# XMC4504.net
KiCad netlist of a schematic drawn in Altium Designer
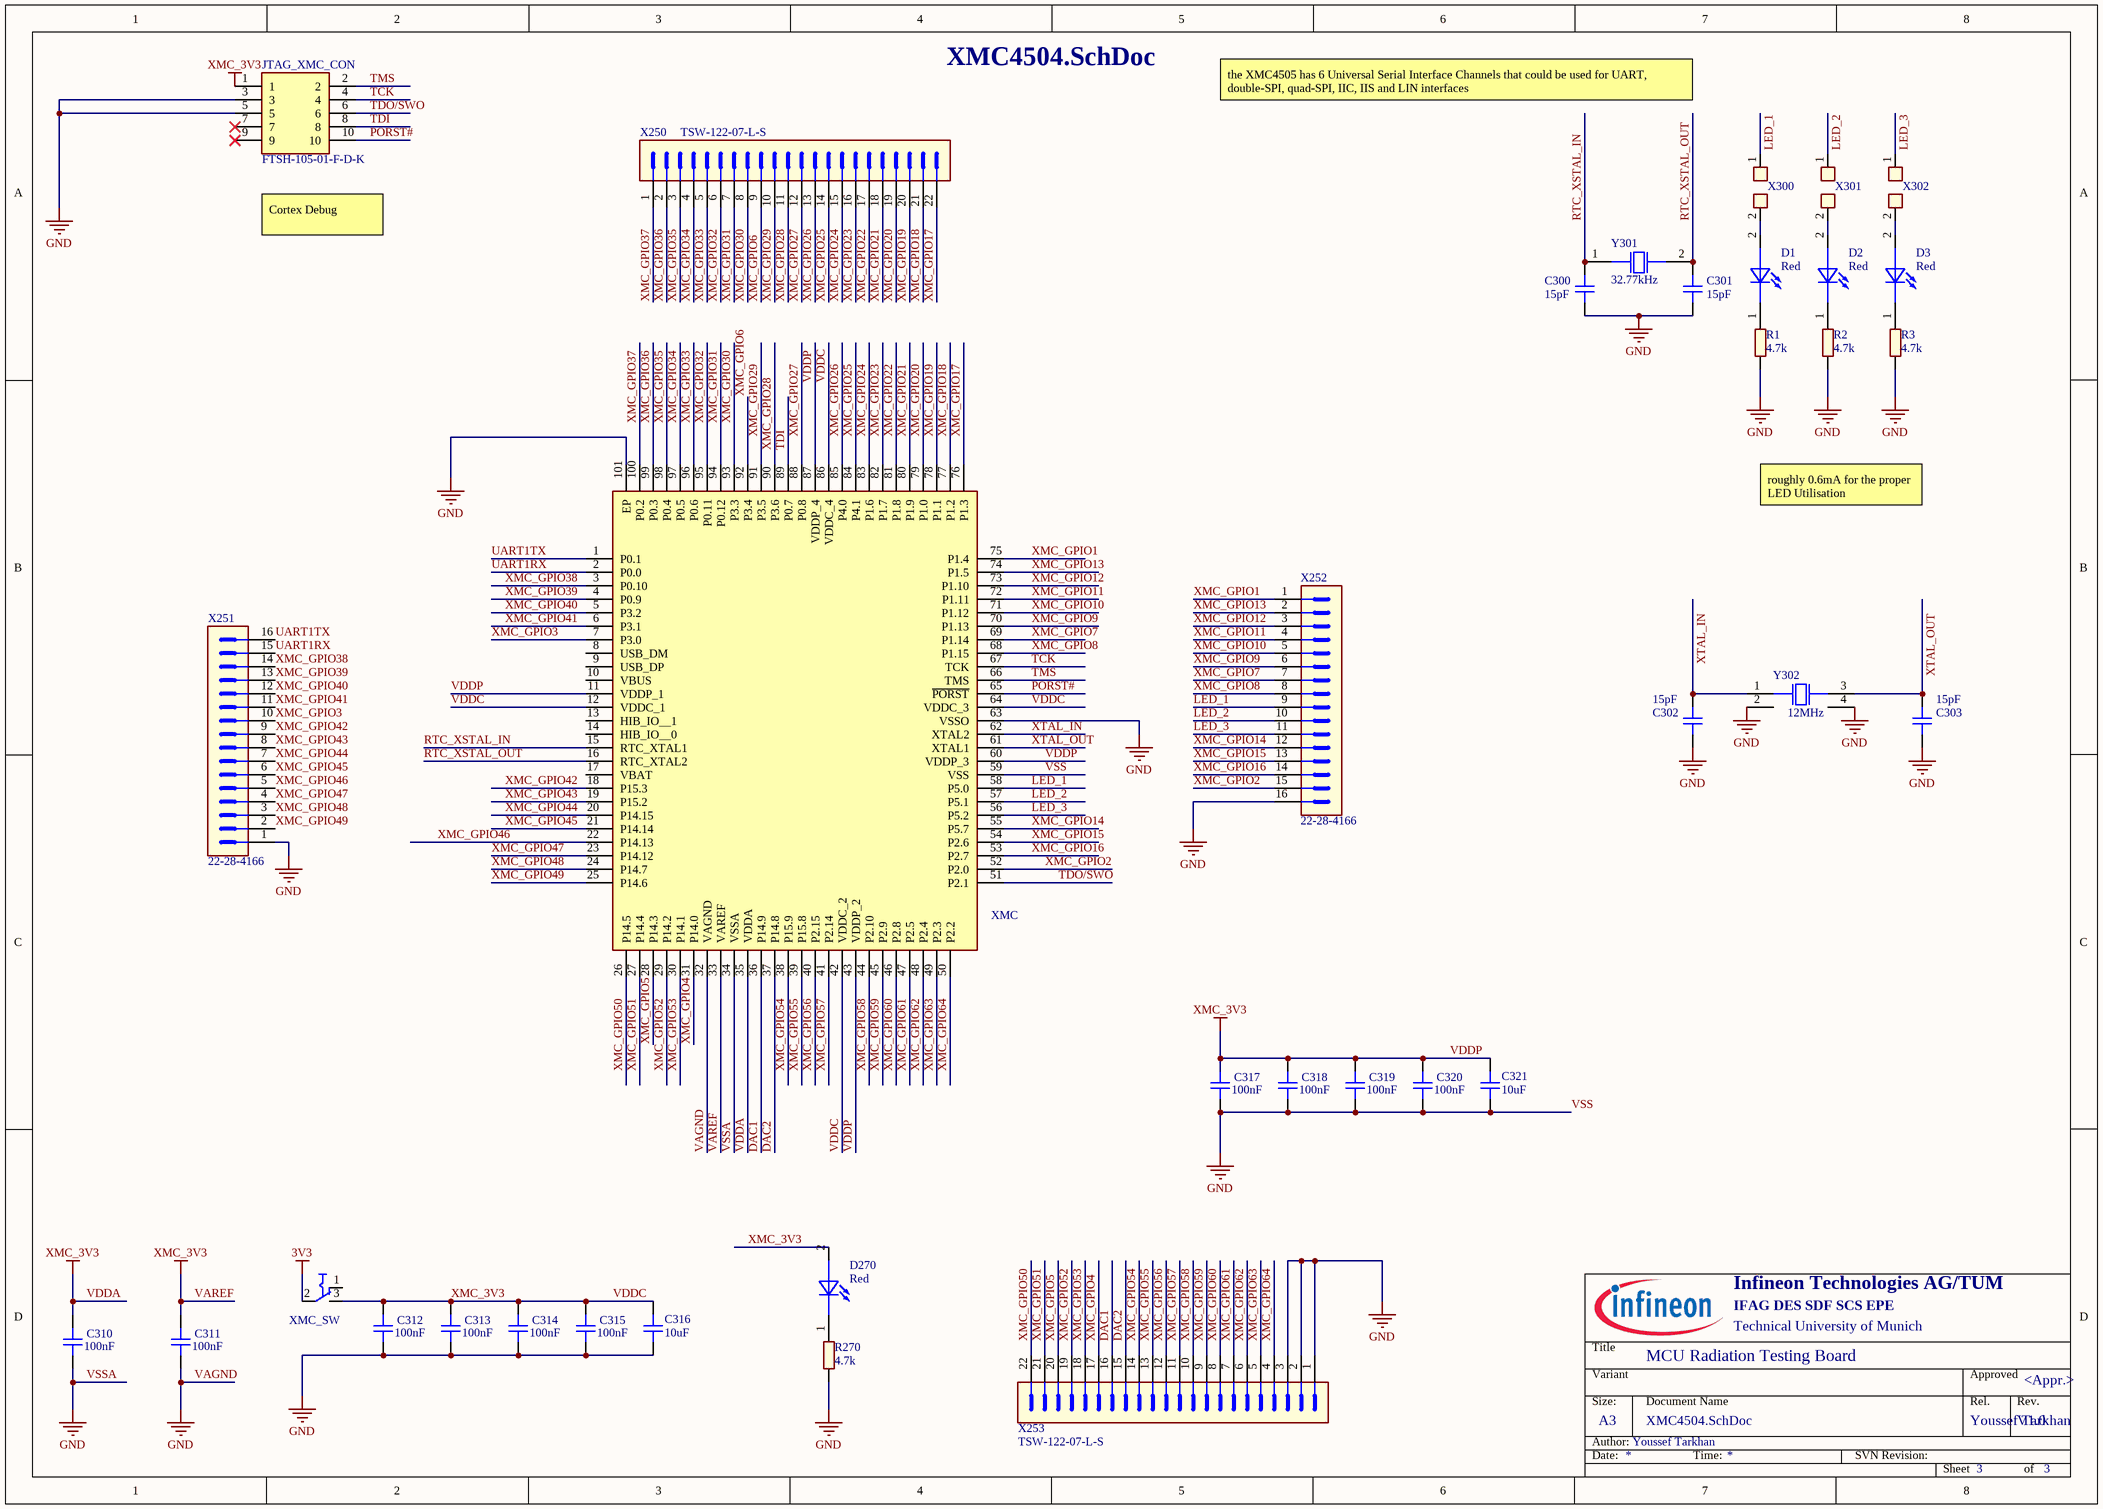
[diagram p0: XMC4504.SchDoc]

(export (version "E")
  (design (tool "Eeschema 10.0.6"))
  (components
    (comp (ref "C300")
      (value "15pF")
      (footprint "CAPC1608X90N")
      (description "CAP / CERA / 15pF / 50V / 2% / C0G (EIA) / NP0 / -55°C to 125°C / 0603(1608) / SMD / -")
      (fields (field (name "LEGACY PARTNUMBER") "CAP01002488") (field (name "MANUFACTURER") "MuRata"))
      (libsource (lib "PCBLibraryData") (part "CAP-SGL-STD-02P_00000001"))
    )
    (comp (ref "C301")
      (value "15pF")
      (footprint "CAPC1608X90N")
      (description "CAP / CERA / 15pF / 50V / 2% / C0G (EIA) / NP0 / -55°C to 125°C / 0603(1608) / SMD / -")
      (fields (field (name "LEGACY PARTNUMBER") "CAP01002488") (field (name "MANUFACTURER") "MuRata"))
      (libsource (lib "PCBLibraryData") (part "CAP-SGL-STD-02P_00000001"))
    )
    (comp (ref "C302")
      (value "15pF")
      (footprint "CAPC1608X90N")
      (description "CAP / CERA / 15pF / 50V / 2% / C0G (EIA) / NP0 / -55°C to 125°C / 0603(1608) / SMD / -")
      (fields (field (name "LEGACY PARTNUMBER") "CAP01002488") (field (name "MANUFACTURER") "MuRata"))
      (libsource (lib "PCBLibraryData") (part "CAP-SGL-STD-02P_00000001"))
    )
    (comp (ref "C303")
      (value "15pF")
      (footprint "CAPC1608X90N")
      (description "CAP / CERA / 15pF / 50V / 2% / C0G (EIA) / NP0 / -55°C to 125°C / 0603(1608) / SMD / -")
      (fields (field (name "LEGACY PARTNUMBER") "CAP01002488") (field (name "MANUFACTURER") "MuRata"))
      (libsource (lib "PCBLibraryData") (part "CAP-SGL-STD-02P_00000001"))
    )
    (comp (ref "C310")
      (value "100nF")
      (footprint "CAPC1608X90N-2")
      (description "CAP / CERA / 100nF / 50V / 10% / X7R (EIA) / -55°C to 125°C / 0603 / SMD / -")
      (fields (field (name "MANUFACTURER") "AVX"))
      (libsource (lib "PCBLibraryData") (part "CAP-SGL-STD-02P_00000001"))
    )
    (comp (ref "C311")
      (value "100nF")
      (footprint "CAPC1608X90N-2")
      (description "CAP / CERA / 100nF / 50V / 10% / X7R (EIA) / -55°C to 125°C / 0603 / SMD / -")
      (fields (field (name "MANUFACTURER") "AVX"))
      (libsource (lib "PCBLibraryData") (part "CAP-SGL-STD-02P_00000001"))
    )
    (comp (ref "C312")
      (value "100nF")
      (footprint "CAPC1608X90N-2")
      (description "CAP / CERA / 100nF / 50V / 10% / X7R (EIA) / -55°C to 125°C / 0603 / SMD / -")
      (fields (field (name "MANUFACTURER") "AVX"))
      (libsource (lib "PCBLibraryData") (part "CAP-SGL-STD-02P_00000001"))
    )
    (comp (ref "C313")
      (value "100nF")
      (footprint "CAPC1608X90N-2")
      (description "CAP / CERA / 100nF / 50V / 10% / X7R (EIA) / -55°C to 125°C / 0603 / SMD / -")
      (fields (field (name "MANUFACTURER") "AVX"))
      (libsource (lib "PCBLibraryData") (part "CAP-SGL-STD-02P_00000001"))
    )
    (comp (ref "C314")
      (value "100nF")
      (footprint "CAPC1608X90N-2")
      (description "CAP / CERA / 100nF / 50V / 10% / X7R (EIA) / -55°C to 125°C / 0603 / SMD / -")
      (fields (field (name "MANUFACTURER") "AVX"))
      (libsource (lib "PCBLibraryData") (part "CAP-SGL-STD-02P_00000001"))
    )
    (comp (ref "C315")
      (value "100nF")
      (footprint "CAPC1608X90N-2")
      (description "CAP / CERA / 100nF / 50V / 10% / X7R (EIA) / -55°C to 125°C / 0603 / SMD / -")
      (fields (field (name "MANUFACTURER") "AVX"))
      (libsource (lib "PCBLibraryData") (part "CAP-SGL-STD-02P_00000001"))
    )
    (comp (ref "C316")
      (value "10uF")
      (footprint "CAPC3216X190N-1")
      (description "CAP / CERA / 10uF / 50V / 20% / X5R (EIA) / -55°C to 85°C / 1206 (3216) / SMD / -")
      (fields (field (name "MANUFACTURER") "Taiyo Yuden"))
      (libsource (lib "PCBLibraryData") (part "CAP-SGL-STD-02P_00000001"))
    )
    (comp (ref "C317")
      (value "100nF")
      (footprint "CAPC1608X90N-2")
      (description "CAP / CERA / 100nF / 50V / 10% / X7R (EIA) / -55°C to 125°C / 0603 / SMD / -")
      (fields (field (name "MANUFACTURER") "AVX"))
      (libsource (lib "PCBLibraryData") (part "CAP-SGL-STD-02P_00000001"))
    )
    (comp (ref "C318")
      (value "100nF")
      (footprint "CAPC1608X90N-2")
      (description "CAP / CERA / 100nF / 50V / 10% / X7R (EIA) / -55°C to 125°C / 0603 / SMD / -")
      (fields (field (name "MANUFACTURER") "AVX"))
      (libsource (lib "PCBLibraryData") (part "CAP-SGL-STD-02P_00000001"))
    )
    (comp (ref "C319")
      (value "100nF")
      (footprint "CAPC1608X90N-2")
      (description "CAP / CERA / 100nF / 50V / 10% / X7R (EIA) / -55°C to 125°C / 0603 / SMD / -")
      (fields (field (name "MANUFACTURER") "AVX"))
      (libsource (lib "PCBLibraryData") (part "CAP-SGL-STD-02P_00000001"))
    )
    (comp (ref "C320")
      (value "100nF")
      (footprint "CAPC1608X90N-2")
      (description "CAP / CERA / 100nF / 50V / 10% / X7R (EIA) / -55°C to 125°C / 0603 / SMD / -")
      (fields (field (name "MANUFACTURER") "AVX"))
      (libsource (lib "PCBLibraryData") (part "CAP-SGL-STD-02P_00000001"))
    )
    (comp (ref "C321")
      (value "10uF")
      (footprint "CAPC3216X190N-1")
      (description "CAP / CERA / 10uF / 50V / 20% / X5R (EIA) / -55°C to 85°C / 1206 (3216) / SMD / -")
      (fields (field (name "MANUFACTURER") "Taiyo Yuden"))
      (libsource (lib "PCBLibraryData") (part "CAP-SGL-STD-02P_00000001"))
    )
    (comp (ref "D1")
      (value "Red")
      (footprint "LEDSC160X80X80-2N-1")
      (description "WL-SMCW SMT Mono-color Chip LED Waterclear, Red,630nm")
      (fields (field (name "MANUFACTURER") "Wurth Elektronik"))
      (libsource (lib "PCBLibraryData") (part "d_led_a"))
    )
    (comp (ref "D2")
      (value "Red")
      (footprint "LEDSC160X80X80-2N-1")
      (description "WL-SMCW SMT Mono-color Chip LED Waterclear, Red,630nm")
      (fields (field (name "MANUFACTURER") "Wurth Elektronik"))
      (libsource (lib "PCBLibraryData") (part "d_led_a"))
    )
    (comp (ref "D3")
      (value "Red")
      (footprint "LEDSC160X80X80-2N-1")
      (description "WL-SMCW SMT Mono-color Chip LED Waterclear, Red,630nm")
      (fields (field (name "MANUFACTURER") "Wurth Elektronik"))
      (libsource (lib "PCBLibraryData") (part "d_led_a"))
    )
    (comp (ref "D270")
      (value "Red")
      (footprint "LEDSC160X80X80-2N-1")
      (description "WL-SMCW SMT Mono-color Chip LED Waterclear, Red,630nm")
      (fields (field (name "MANUFACTURER") "Wurth Elektronik"))
      (libsource (lib "PCBLibraryData") (part "d_led_a"))
    )
    (comp (ref "JTAG_XMC_CON")
      (value "FTSH-105-01-F-D-K")
      (footprint "SamacSys:FTSH-105-XX-YYY-D-K")
      (description "Connector")
      (fields (field (name "MOUSER2 PART NUMBER") "200-FTSH10501FDK"))
      (libsource (lib "*") (part "FTSH-105-01-F-D-K"))
    )
    (comp (ref "R1")
      (value "4.7k")
      (footprint "RESC1609X55N")
      (description "RES / STD / 4.7k / 100mW / 1% / 100ppm/K / -55°C to 155°C / 1.60mm L X 0.85mm W X 0.55mm H / - / -")
      (fields (field (name "MANUFACTURER") "Panasonic"))
      (libsource (lib "PCBLibraryData") (part "RES-SGL-STD-02P_00000006"))
    )
    (comp (ref "R2")
      (value "4.7k")
      (footprint "RESC1609X55N")
      (description "RES / STD / 4.7k / 100mW / 1% / 100ppm/K / -55°C to 155°C / 1.60mm L X 0.85mm W X 0.55mm H / - / -")
      (fields (field (name "MANUFACTURER") "Panasonic"))
      (libsource (lib "PCBLibraryData") (part "RES-SGL-STD-02P_00000006"))
    )
    (comp (ref "R3")
      (value "4.7k")
      (footprint "RESC1609X55N")
      (description "RES / STD / 4.7k / 100mW / 1% / 100ppm/K / -55°C to 155°C / 1.60mm L X 0.85mm W X 0.55mm H / - / -")
      (fields (field (name "MANUFACTURER") "Panasonic"))
      (libsource (lib "PCBLibraryData") (part "RES-SGL-STD-02P_00000006"))
    )
    (comp (ref "R270")
      (value "4.7k")
      (footprint "RESC1609X55N")
      (description "RES / STD / 4.7k / 100mW / 1% / 100ppm/K / -55°C to 155°C / 1.60mm L X 0.85mm W X 0.55mm H / - / -")
      (fields (field (name "MANUFACTURER") "Panasonic"))
      (libsource (lib "PCBLibraryData") (part "RES-SGL-STD-02P_00000006"))
    )
    (comp (ref "X250")
      (value "TSW-122-07-L-S")
      (footprint "CON-M-THT-TSW-122-07-L-S")
      (description "Through hole .025 SQ Post Header, 2.54mm pitch, 22 pin, vertical, single row")
      (fields (field (name "LEGACY PARTNUMBER") "CON01500868") (field (name "MANUFACTURER") "Samtec"))
      (libsource (lib "PCBLibraryData") (part "Header 22"))
    )
    (comp (ref "X251")
      (value "22-28-4166")
      (footprint "HDRV16W66P254_1X16_4064X249X838B")
      (fields (field (name "LEGACY PARTNUMBER") "CON01500040") (field (name "MANUFACTURER") "Molex"))
      (libsource (lib "") (part "Header 16_1"))
    )
    (comp (ref "X252")
      (value "22-28-4166")
      (footprint "HDRV16W66P254_1X16_4064X249X838B")
      (fields (field (name "LEGACY PARTNUMBER") "CON01500040") (field (name "MANUFACTURER") "Molex"))
      (libsource (lib "PCBLibraryData") (part "Header 16"))
    )
    (comp (ref "X253")
      (value "TSW-122-07-L-S")
      (footprint "CON-M-THT-TSW-122-07-L-S")
      (description "Through hole .025 SQ Post Header, 2.54mm pitch, 22 pin, vertical, single row")
      (fields (field (name "LEGACY PARTNUMBER") "CON01500868") (field (name "MANUFACTURER") "Samtec"))
      (libsource (lib "PCBLibraryData") (part "Header 22"))
    )
    (comp (ref "X300")
      (value "Solder Jumper 2 Pins")
      (footprint "SOLDER_BRIDGE_0.7X1.299PAD")
      (fields
        (field (name "LEGACY PARTNUMBER") "CON01500959")
        (field (name "MANUFACTURER") "Infineon Technologies")
      )
      (libsource (lib "PCBLibraryData") (part "SJP_2P"))
    )
    (comp (ref "X301")
      (value "Solder Jumper 2 Pins")
      (footprint "SOLDER_BRIDGE_0.7X1.299PAD")
      (fields
        (field (name "LEGACY PARTNUMBER") "CON01500959")
        (field (name "MANUFACTURER") "Infineon Technologies")
      )
      (libsource (lib "PCBLibraryData") (part "SJP_2P"))
    )
    (comp (ref "X302")
      (value "Solder Jumper 2 Pins")
      (footprint "SOLDER_BRIDGE_0.7X1.299PAD")
      (fields
        (field (name "LEGACY PARTNUMBER") "CON01500959")
        (field (name "MANUFACTURER") "Infineon Technologies")
      )
      (libsource (lib "PCBLibraryData") (part "SJP_2P"))
    )
    (comp (ref "XMC")
      (value "XMC4504F100F512ACXQMA1")
      (footprint "SamacSys:QFP50P1600X1600X160-101N")
      (description "Integrated Circuit")
      (libsource (lib "*") (part "XMC4504F100F512ACXQMA1"))
    )
    (comp (ref "XMC_SW")
      (value "CL-SB-12A-01T")
      (footprint "SW-SMD-CL-SB-12A-01T")
      (description "Slid Switch, 12V, 200mA")
      (fields (field (name "MANUFACTURER") "NIDEC COPAL ELECTRONICS, Inc."))
      (libsource (lib "PCBLibraryData") (part "sw_co213_3p"))
    )
    (comp (ref "Y301")
      (value "32.77kHz")
      (footprint "XTAL-SMD-NX3215SA-32.768K-STD-MUS-2")
      (description "CRYSTAL 32.7680KHZ 12.5PF SMD")
      (fields (field (name "MANUFACTURER") "CTS Electronic Component"))
      (libsource (lib "PCBLibraryData") (part "y_std_a"))
    )
    (comp (ref "Y302")
      (value "12MHz")
      (footprint "XTAL-SMD-NX3225SA")
      (description "SMD Crystal Unit for Automotive Application, 12.000MHz")
      (fields
        (field (name "LEGACY PARTNUMBER") "IC02600619")
        (field (name "MANUFACTURER") "Nihon Dempa Kogyo")
      )
      (libsource (lib "PCBLibraryData") (part "y_std_4p-1"))
    )
  )
  (nets
    (net (code "1") (name "/DAC1") (class "Default")
      (node (ref "X253") (pin "16") (pinfunction "16_16") (pintype "passive"))
      (node (ref "XMC") (pin "36") (pinfunction "P14.9_36") (pintype "passive"))
    )
    (net (code "2") (name "/DAC2") (class "Default")
      (node (ref "X253") (pin "15") (pinfunction "15_15") (pintype "passive"))
      (node (ref "XMC") (pin "37") (pinfunction "P14.8_37") (pintype "passive"))
    )
    (net (code "3") (name "/LED_1") (class "Default")
      (node (ref "X252") (pin "9") (pinfunction "9_9") (pintype "passive"))
      (node (ref "X300") (pin "1") (pinfunction "1_1") (pintype "passive"))
      (node (ref "XMC") (pin "58") (pinfunction "P5.0_58") (pintype "passive"))
    )
    (net (code "4") (name "/LED_2") (class "Default")
      (node (ref "X252") (pin "10") (pinfunction "10_10") (pintype "passive"))
      (node (ref "X301") (pin "1") (pinfunction "1_1") (pintype "passive"))
      (node (ref "XMC") (pin "57") (pinfunction "P5.1_57") (pintype "passive"))
    )
    (net (code "5") (name "/LED_3") (class "Default")
      (node (ref "X252") (pin "11") (pinfunction "11_11") (pintype "passive"))
      (node (ref "X302") (pin "1") (pinfunction "1_1") (pintype "passive"))
      (node (ref "XMC") (pin "56") (pinfunction "P5.2_56") (pintype "passive"))
    )
    (net (code "6") (name "/PORST#") (class "Default")
      (node (ref "JTAG_XMC_CON") (pin "10") (pinfunction "10_10") (pintype "passive"))
      (node (ref "XMC") (pin "65") (pinfunction "~{PORST}_65") (pintype "passive"))
    )
    (net (code "7") (name "/RTC_XSTAL_IN") (class "Default")
      (node (ref "C300") (pin "2") (pinfunction "2_2") (pintype "passive"))
      (node (ref "XMC") (pin "15") (pinfunction "RTC_XTAL1_15") (pintype "passive"))
      (node (ref "Y301") (pin "1") (pinfunction "1_1") (pintype "passive"))
    )
    (net (code "8") (name "/RTC_XSTAL_OUT") (class "Default")
      (node (ref "C301") (pin "2") (pinfunction "2_2") (pintype "passive"))
      (node (ref "XMC") (pin "16") (pinfunction "RTC_XTAL2_16") (pintype "passive"))
      (node (ref "Y301") (pin "2") (pinfunction "2_2") (pintype "passive"))
    )
    (net (code "9") (name "/TCK") (class "Default")
      (node (ref "JTAG_XMC_CON") (pin "4") (pinfunction "4_4") (pintype "passive"))
      (node (ref "XMC") (pin "67") (pinfunction "TCK_67") (pintype "passive"))
    )
    (net (code "10") (name "/TDI") (class "Default")
      (node (ref "JTAG_XMC_CON") (pin "8") (pinfunction "8_8") (pintype "passive"))
      (node (ref "XMC") (pin "89") (pinfunction "P0.7_89") (pintype "passive"))
    )
    (net (code "11") (name "/TDO{slash}SWO") (class "Default")
      (node (ref "JTAG_XMC_CON") (pin "6") (pinfunction "6_6") (pintype "passive"))
      (node (ref "XMC") (pin "51") (pinfunction "P2.1_51") (pintype "passive"))
    )
    (net (code "12") (name "/TMS") (class "Default")
      (node (ref "JTAG_XMC_CON") (pin "2") (pinfunction "2_2") (pintype "passive"))
      (node (ref "XMC") (pin "66") (pinfunction "TMS_66") (pintype "passive"))
    )
    (net (code "13") (name "/UART1RX") (class "Default")
      (node (ref "X251") (pin "15") (pinfunction "15_15") (pintype "passive"))
      (node (ref "XMC") (pin "2") (pinfunction "P0.0_2") (pintype "passive"))
    )
    (net (code "14") (name "/UART1TX") (class "Default")
      (node (ref "X251") (pin "16") (pinfunction "16_16") (pintype "passive"))
      (node (ref "XMC") (pin "1") (pinfunction "P0.1_1") (pintype "passive"))
    )
    (net (code "15") (name "/XMC_GPIO1") (class "Default")
      (node (ref "X252") (pin "1") (pinfunction "1_1") (pintype "passive"))
      (node (ref "XMC") (pin "75") (pinfunction "P1.4_75") (pintype "passive"))
    )
    (net (code "16") (name "/XMC_GPIO2") (class "Default")
      (node (ref "X252") (pin "15") (pinfunction "15_15") (pintype "passive"))
      (node (ref "XMC") (pin "52") (pinfunction "P2.0_52") (pintype "passive"))
    )
    (net (code "17") (name "/XMC_GPIO3") (class "Default")
      (node (ref "X251") (pin "10") (pinfunction "10_10") (pintype "passive"))
      (node (ref "XMC") (pin "7") (pinfunction "P3.0_7") (pintype "passive"))
    )
    (net (code "18") (name "/XMC_GPIO4") (class "Default")
      (node (ref "X253") (pin "17") (pinfunction "17_17") (pintype "passive"))
      (node (ref "XMC") (pin "31") (pinfunction "P14.0_31") (pintype "passive"))
    )
    (net (code "19") (name "/XMC_GPIO5") (class "Default")
      (node (ref "X253") (pin "20") (pinfunction "20_20") (pintype "passive"))
      (node (ref "XMC") (pin "28") (pinfunction "P14.3_28") (pintype "passive"))
    )
    (net (code "20") (name "/XMC_GPIO6") (class "Default")
      (node (ref "X250") (pin "9") (pinfunction "9_9") (pintype "passive"))
      (node (ref "XMC") (pin "92") (pinfunction "P3.4_92") (pintype "passive"))
    )
    (net (code "21") (name "/XMC_GPIO7") (class "Default")
      (node (ref "X252") (pin "7") (pinfunction "7_7") (pintype "passive"))
      (node (ref "XMC") (pin "69") (pinfunction "P1.14_69") (pintype "passive"))
    )
    (net (code "22") (name "/XMC_GPIO8") (class "Default")
      (node (ref "X252") (pin "8") (pinfunction "8_8") (pintype "passive"))
      (node (ref "XMC") (pin "68") (pinfunction "P1.15_68") (pintype "passive"))
    )
    (net (code "23") (name "/XMC_GPIO9") (class "Default")
      (node (ref "X252") (pin "6") (pinfunction "6_6") (pintype "passive"))
      (node (ref "XMC") (pin "70") (pinfunction "P1.13_70") (pintype "passive"))
    )
    (net (code "24") (name "/XMC_GPIO10") (class "Default")
      (node (ref "X252") (pin "5") (pinfunction "5_5") (pintype "passive"))
      (node (ref "XMC") (pin "71") (pinfunction "P1.12_71") (pintype "passive"))
    )
    (net (code "25") (name "/XMC_GPIO11") (class "Default")
      (node (ref "X252") (pin "4") (pinfunction "4_4") (pintype "passive"))
      (node (ref "XMC") (pin "72") (pinfunction "P1.11_72") (pintype "passive"))
    )
    (net (code "26") (name "/XMC_GPIO12") (class "Default")
      (node (ref "X252") (pin "3") (pinfunction "3_3") (pintype "passive"))
      (node (ref "XMC") (pin "73") (pinfunction "P1.10_73") (pintype "passive"))
    )
    (net (code "27") (name "/XMC_GPIO13") (class "Default")
      (node (ref "X252") (pin "2") (pinfunction "2_2") (pintype "passive"))
      (node (ref "XMC") (pin "74") (pinfunction "P1.5_74") (pintype "passive"))
    )
    (net (code "28") (name "/XMC_GPIO14") (class "Default")
      (node (ref "X252") (pin "12") (pinfunction "12_12") (pintype "passive"))
      (node (ref "XMC") (pin "55") (pinfunction "P5.7_55") (pintype "passive"))
    )
    (net (code "29") (name "/XMC_GPIO15") (class "Default")
      (node (ref "X252") (pin "13") (pinfunction "13_13") (pintype "passive"))
      (node (ref "XMC") (pin "54") (pinfunction "P2.6_54") (pintype "passive"))
    )
    (net (code "30") (name "/XMC_GPIO16") (class "Default")
      (node (ref "X252") (pin "14") (pinfunction "14_14") (pintype "passive"))
      (node (ref "XMC") (pin "53") (pinfunction "P2.7_53") (pintype "passive"))
    )
    (net (code "31") (name "/XMC_GPIO17") (class "Default")
      (node (ref "X250") (pin "22") (pinfunction "22_22") (pintype "passive"))
      (node (ref "XMC") (pin "76") (pinfunction "P1.3_76") (pintype "passive"))
    )
    (net (code "32") (name "/XMC_GPIO18") (class "Default")
      (node (ref "X250") (pin "21") (pinfunction "21_21") (pintype "passive"))
      (node (ref "XMC") (pin "77") (pinfunction "P1.2_77") (pintype "passive"))
    )
    (net (code "33") (name "/XMC_GPIO19") (class "Default")
      (node (ref "X250") (pin "20") (pinfunction "20_20") (pintype "passive"))
      (node (ref "XMC") (pin "78") (pinfunction "P1.1_78") (pintype "passive"))
    )
    (net (code "34") (name "/XMC_GPIO20") (class "Default")
      (node (ref "X250") (pin "19") (pinfunction "19_19") (pintype "passive"))
      (node (ref "XMC") (pin "79") (pinfunction "P1.0_79") (pintype "passive"))
    )
    (net (code "35") (name "/XMC_GPIO21") (class "Default")
      (node (ref "X250") (pin "18") (pinfunction "18_18") (pintype "passive"))
      (node (ref "XMC") (pin "80") (pinfunction "P1.9_80") (pintype "passive"))
    )
    (net (code "36") (name "/XMC_GPIO22") (class "Default")
      (node (ref "X250") (pin "17") (pinfunction "17_17") (pintype "passive"))
      (node (ref "XMC") (pin "81") (pinfunction "P1.8_81") (pintype "passive"))
    )
    (net (code "37") (name "/XMC_GPIO23") (class "Default")
      (node (ref "X250") (pin "16") (pinfunction "16_16") (pintype "passive"))
      (node (ref "XMC") (pin "82") (pinfunction "P1.7_82") (pintype "passive"))
    )
    (net (code "38") (name "/XMC_GPIO24") (class "Default")
      (node (ref "X250") (pin "15") (pinfunction "15_15") (pintype "passive"))
      (node (ref "XMC") (pin "83") (pinfunction "P1.6_83") (pintype "passive"))
    )
    (net (code "39") (name "/XMC_GPIO25") (class "Default")
      (node (ref "X250") (pin "14") (pinfunction "14_14") (pintype "passive"))
      (node (ref "XMC") (pin "84") (pinfunction "P4.1_84") (pintype "passive"))
    )
    (net (code "40") (name "/XMC_GPIO26") (class "Default")
      (node (ref "X250") (pin "13") (pinfunction "13_13") (pintype "passive"))
      (node (ref "XMC") (pin "85") (pinfunction "P4.0_85") (pintype "passive"))
    )
    (net (code "41") (name "/XMC_GPIO27") (class "Default")
      (node (ref "X250") (pin "12") (pinfunction "12_12") (pintype "passive"))
      (node (ref "XMC") (pin "88") (pinfunction "P0.8_88") (pintype "passive"))
    )
    (net (code "42") (name "/XMC_GPIO28") (class "Default")
      (node (ref "X250") (pin "11") (pinfunction "11_11") (pintype "passive"))
      (node (ref "XMC") (pin "90") (pinfunction "P3.6_90") (pintype "passive"))
    )
    (net (code "43") (name "/XMC_GPIO29") (class "Default")
      (node (ref "X250") (pin "10") (pinfunction "10_10") (pintype "passive"))
      (node (ref "XMC") (pin "91") (pinfunction "P3.5_91") (pintype "passive"))
    )
    (net (code "44") (name "/XMC_GPIO30") (class "Default")
      (node (ref "X250") (pin "8") (pinfunction "8_8") (pintype "passive"))
      (node (ref "XMC") (pin "93") (pinfunction "P3.3_93") (pintype "passive"))
    )
    (net (code "45") (name "/XMC_GPIO31") (class "Default")
      (node (ref "X250") (pin "7") (pinfunction "7_7") (pintype "passive"))
      (node (ref "XMC") (pin "94") (pinfunction "P0.12_94") (pintype "passive"))
    )
    (net (code "46") (name "/XMC_GPIO32") (class "Default")
      (node (ref "X250") (pin "6") (pinfunction "6_6") (pintype "passive"))
      (node (ref "XMC") (pin "95") (pinfunction "P0.11_95") (pintype "passive"))
    )
    (net (code "47") (name "/XMC_GPIO33") (class "Default")
      (node (ref "X250") (pin "5") (pinfunction "5_5") (pintype "passive"))
      (node (ref "XMC") (pin "96") (pinfunction "P0.6_96") (pintype "passive"))
    )
    (net (code "48") (name "/XMC_GPIO34") (class "Default")
      (node (ref "X250") (pin "4") (pinfunction "4_4") (pintype "passive"))
      (node (ref "XMC") (pin "97") (pinfunction "P0.5_97") (pintype "passive"))
    )
    (net (code "49") (name "/XMC_GPIO35") (class "Default")
      (node (ref "X250") (pin "3") (pinfunction "3_3") (pintype "passive"))
      (node (ref "XMC") (pin "98") (pinfunction "P0.4_98") (pintype "passive"))
    )
    (net (code "50") (name "/XMC_GPIO36") (class "Default")
      (node (ref "X250") (pin "2") (pinfunction "2_2") (pintype "passive"))
      (node (ref "XMC") (pin "99") (pinfunction "P0.3_99") (pintype "passive"))
    )
    (net (code "51") (name "/XMC_GPIO37") (class "Default")
      (node (ref "X250") (pin "1") (pinfunction "1_1") (pintype "passive"))
      (node (ref "XMC") (pin "100") (pinfunction "P0.2_100") (pintype "passive"))
    )
    (net (code "52") (name "/XMC_GPIO38") (class "Default")
      (node (ref "X251") (pin "14") (pinfunction "14_14") (pintype "passive"))
      (node (ref "XMC") (pin "3") (pinfunction "P0.10_3") (pintype "passive"))
    )
    (net (code "53") (name "/XMC_GPIO39") (class "Default")
      (node (ref "X251") (pin "13") (pinfunction "13_13") (pintype "passive"))
      (node (ref "XMC") (pin "4") (pinfunction "P0.9_4") (pintype "passive"))
    )
    (net (code "54") (name "/XMC_GPIO40") (class "Default")
      (node (ref "X251") (pin "12") (pinfunction "12_12") (pintype "passive"))
      (node (ref "XMC") (pin "5") (pinfunction "P3.2_5") (pintype "passive"))
    )
    (net (code "55") (name "/XMC_GPIO41") (class "Default")
      (node (ref "X251") (pin "11") (pinfunction "11_11") (pintype "passive"))
      (node (ref "XMC") (pin "6") (pinfunction "P3.1_6") (pintype "passive"))
    )
    (net (code "56") (name "/XMC_GPIO42") (class "Default")
      (node (ref "X251") (pin "9") (pinfunction "9_9") (pintype "passive"))
      (node (ref "XMC") (pin "18") (pinfunction "P15.3_18") (pintype "passive"))
    )
    (net (code "57") (name "/XMC_GPIO43") (class "Default")
      (node (ref "X251") (pin "8") (pinfunction "8_8") (pintype "passive"))
      (node (ref "XMC") (pin "19") (pinfunction "P15.2_19") (pintype "passive"))
    )
    (net (code "58") (name "/XMC_GPIO44") (class "Default")
      (node (ref "X251") (pin "7") (pinfunction "7_7") (pintype "passive"))
      (node (ref "XMC") (pin "20") (pinfunction "P14.15_20") (pintype "passive"))
    )
    (net (code "59") (name "/XMC_GPIO45") (class "Default")
      (node (ref "X251") (pin "6") (pinfunction "6_6") (pintype "passive"))
      (node (ref "XMC") (pin "21") (pinfunction "P14.14_21") (pintype "passive"))
    )
    (net (code "60") (name "/XMC_GPIO46") (class "Default")
      (node (ref "X251") (pin "5") (pinfunction "5_5") (pintype "passive"))
      (node (ref "XMC") (pin "22") (pinfunction "P14.13_22") (pintype "passive"))
    )
    (net (code "61") (name "/XMC_GPIO47") (class "Default")
      (node (ref "X251") (pin "4") (pinfunction "4_4") (pintype "passive"))
      (node (ref "XMC") (pin "23") (pinfunction "P14.12_23") (pintype "passive"))
    )
    (net (code "62") (name "/XMC_GPIO48") (class "Default")
      (node (ref "X251") (pin "3") (pinfunction "3_3") (pintype "passive"))
      (node (ref "XMC") (pin "24") (pinfunction "P14.7_24") (pintype "passive"))
    )
    (net (code "63") (name "/XMC_GPIO49") (class "Default")
      (node (ref "X251") (pin "2") (pinfunction "2_2") (pintype "passive"))
      (node (ref "XMC") (pin "25") (pinfunction "P14.6_25") (pintype "passive"))
    )
    (net (code "64") (name "/XMC_GPIO50") (class "Default")
      (node (ref "X253") (pin "22") (pinfunction "22_22") (pintype "passive"))
      (node (ref "XMC") (pin "26") (pinfunction "P14.5_26") (pintype "passive"))
    )
    (net (code "65") (name "/XMC_GPIO51") (class "Default")
      (node (ref "X253") (pin "21") (pinfunction "21_21") (pintype "passive"))
      (node (ref "XMC") (pin "27") (pinfunction "P14.4_27") (pintype "passive"))
    )
    (net (code "66") (name "/XMC_GPIO52") (class "Default")
      (node (ref "X253") (pin "19") (pinfunction "19_19") (pintype "passive"))
      (node (ref "XMC") (pin "29") (pinfunction "P14.2_29") (pintype "passive"))
    )
    (net (code "67") (name "/XMC_GPIO53") (class "Default")
      (node (ref "X253") (pin "18") (pinfunction "18_18") (pintype "passive"))
      (node (ref "XMC") (pin "30") (pinfunction "P14.1_30") (pintype "passive"))
    )
    (net (code "68") (name "/XMC_GPIO54") (class "Default")
      (node (ref "X253") (pin "14") (pinfunction "14_14") (pintype "passive"))
      (node (ref "XMC") (pin "38") (pinfunction "P15.9_38") (pintype "passive"))
    )
    (net (code "69") (name "/XMC_GPIO55") (class "Default")
      (node (ref "X253") (pin "13") (pinfunction "13_13") (pintype "passive"))
      (node (ref "XMC") (pin "39") (pinfunction "P15.8_39") (pintype "passive"))
    )
    (net (code "70") (name "/XMC_GPIO56") (class "Default")
      (node (ref "X253") (pin "12") (pinfunction "12_12") (pintype "passive"))
      (node (ref "XMC") (pin "40") (pinfunction "P2.15_40") (pintype "passive"))
    )
    (net (code "71") (name "/XMC_GPIO57") (class "Default")
      (node (ref "X253") (pin "11") (pinfunction "11_11") (pintype "passive"))
      (node (ref "XMC") (pin "41") (pinfunction "P2.14_41") (pintype "passive"))
    )
    (net (code "72") (name "/XMC_GPIO58") (class "Default")
      (node (ref "X253") (pin "10") (pinfunction "10_10") (pintype "passive"))
      (node (ref "XMC") (pin "44") (pinfunction "P2.10_44") (pintype "passive"))
    )
    (net (code "73") (name "/XMC_GPIO59") (class "Default")
      (node (ref "X253") (pin "9") (pinfunction "9_9") (pintype "passive"))
      (node (ref "XMC") (pin "45") (pinfunction "P2.9_45") (pintype "passive"))
    )
    (net (code "74") (name "/XMC_GPIO60") (class "Default")
      (node (ref "X253") (pin "8") (pinfunction "8_8") (pintype "passive"))
      (node (ref "XMC") (pin "46") (pinfunction "P2.8_46") (pintype "passive"))
    )
    (net (code "75") (name "/XMC_GPIO61") (class "Default")
      (node (ref "X253") (pin "7") (pinfunction "7_7") (pintype "passive"))
      (node (ref "XMC") (pin "47") (pinfunction "P2.5_47") (pintype "passive"))
    )
    (net (code "76") (name "/XMC_GPIO62") (class "Default")
      (node (ref "X253") (pin "6") (pinfunction "6_6") (pintype "passive"))
      (node (ref "XMC") (pin "48") (pinfunction "P2.4_48") (pintype "passive"))
    )
    (net (code "77") (name "/XMC_GPIO63") (class "Default")
      (node (ref "X253") (pin "5") (pinfunction "5_5") (pintype "passive"))
      (node (ref "XMC") (pin "49") (pinfunction "P2.3_49") (pintype "passive"))
    )
    (net (code "78") (name "/XMC_GPIO64") (class "Default")
      (node (ref "X253") (pin "4") (pinfunction "4_4") (pintype "passive"))
      (node (ref "XMC") (pin "50") (pinfunction "P2.2_50") (pintype "passive"))
    )
    (net (code "79") (name "/XTAL_IN") (class "Default")
      (node (ref "C302") (pin "2") (pinfunction "2_2") (pintype "passive"))
      (node (ref "XMC") (pin "62") (pinfunction "XTAL2_62") (pintype "passive"))
      (node (ref "Y302") (pin "1") (pinfunction "1_1") (pintype "passive"))
    )
    (net (code "80") (name "/XTAL_OUT") (class "Default")
      (node (ref "C303") (pin "2") (pinfunction "2_2") (pintype "passive"))
      (node (ref "XMC") (pin "61") (pinfunction "XTAL1_61") (pintype "passive"))
      (node (ref "Y302") (pin "3") (pinfunction "3_3") (pintype "passive"))
    )
    (net (code "81") (name "3V3") (class "Default")
      (node (ref "XMC_SW") (pin "2") (pinfunction "2_2") (pintype "passive"))
    )
    (net (code "82") (name "GND") (class "Default")
      (node (ref "C300") (pin "1") (pinfunction "1_1") (pintype "passive"))
      (node (ref "C301") (pin "1") (pinfunction "1_1") (pintype "passive"))
      (node (ref "C302") (pin "1") (pinfunction "1_1") (pintype "passive"))
      (node (ref "C303") (pin "1") (pinfunction "1_1") (pintype "passive"))
      (node (ref "C310") (pin "2") (pinfunction "2_2") (pintype "passive"))
      (node (ref "C311") (pin "2") (pinfunction "2_2") (pintype "passive"))
      (node (ref "C312") (pin "2") (pinfunction "2_2") (pintype "passive"))
      (node (ref "C313") (pin "2") (pinfunction "2_2") (pintype "passive"))
      (node (ref "C314") (pin "2") (pinfunction "2_2") (pintype "passive"))
      (node (ref "C315") (pin "2") (pinfunction "2_2") (pintype "passive"))
      (node (ref "C316") (pin "1") (pinfunction "1_1") (pintype "passive"))
      (node (ref "C317") (pin "2") (pinfunction "2_2") (pintype "passive"))
      (node (ref "C318") (pin "2") (pinfunction "2_2") (pintype "passive"))
      (node (ref "C319") (pin "2") (pinfunction "2_2") (pintype "passive"))
      (node (ref "C320") (pin "2") (pinfunction "2_2") (pintype "passive"))
      (node (ref "C321") (pin "1") (pinfunction "1_1") (pintype "passive"))
      (node (ref "JTAG_XMC_CON") (pin "3") (pinfunction "3_3") (pintype "passive"))
      (node (ref "JTAG_XMC_CON") (pin "5") (pinfunction "5_5") (pintype "passive"))
      (node (ref "R1") (pin "1") (pinfunction "1_1") (pintype "passive"))
      (node (ref "R2") (pin "1") (pinfunction "1_1") (pintype "passive"))
      (node (ref "R270") (pin "1") (pinfunction "1_1") (pintype "passive"))
      (node (ref "R3") (pin "1") (pinfunction "1_1") (pintype "passive"))
      (node (ref "X251") (pin "1") (pinfunction "1_1") (pintype "passive"))
      (node (ref "X252") (pin "16") (pinfunction "16_16") (pintype "passive"))
      (node (ref "X253") (pin "1") (pinfunction "1_1") (pintype "passive"))
      (node (ref "X253") (pin "2") (pinfunction "2_2") (pintype "passive"))
      (node (ref "X253") (pin "3") (pinfunction "3_3") (pintype "passive"))
      (node (ref "XMC") (pin "101") (pinfunction "EP_101") (pintype "passive"))
      (node (ref "XMC") (pin "32") (pinfunction "VAGND_32") (pintype "passive"))
      (node (ref "XMC") (pin "34") (pinfunction "VSSA_34") (pintype "passive"))
      (node (ref "XMC") (pin "59") (pinfunction "VSS_59") (pintype "passive"))
      (node (ref "XMC") (pin "63") (pinfunction "VSSO_63") (pintype "passive"))
      (node (ref "Y302") (pin "2") (pinfunction "2_2") (pintype "power_in"))
      (node (ref "Y302") (pin "4") (pinfunction "4_4") (pintype "power_in"))
    )
    (net (code "83") (name "Net-(D1-Anode)") (class "Default")
      (node (ref "D1") (pin "2") (pinfunction "Anode_2") (pintype "passive"))
      (node (ref "X300") (pin "2") (pinfunction "2_2") (pintype "passive"))
    )
    (net (code "84") (name "Net-(D1-Cathode)") (class "Default")
      (node (ref "D1") (pin "1") (pinfunction "Cathode_1") (pintype "passive"))
      (node (ref "R1") (pin "2") (pinfunction "2_2") (pintype "passive"))
    )
    (net (code "85") (name "Net-(D2-Anode)") (class "Default")
      (node (ref "D2") (pin "2") (pinfunction "Anode_2") (pintype "passive"))
      (node (ref "X301") (pin "2") (pinfunction "2_2") (pintype "passive"))
    )
    (net (code "86") (name "Net-(D2-Cathode)") (class "Default")
      (node (ref "D2") (pin "1") (pinfunction "Cathode_1") (pintype "passive"))
      (node (ref "R2") (pin "2") (pinfunction "2_2") (pintype "passive"))
    )
    (net (code "87") (name "Net-(D3-Anode)") (class "Default")
      (node (ref "D3") (pin "2") (pinfunction "Anode_2") (pintype "passive"))
      (node (ref "X302") (pin "2") (pinfunction "2_2") (pintype "passive"))
    )
    (net (code "88") (name "Net-(D3-Cathode)") (class "Default")
      (node (ref "D3") (pin "1") (pinfunction "Cathode_1") (pintype "passive"))
      (node (ref "R3") (pin "2") (pinfunction "2_2") (pintype "passive"))
    )
    (net (code "89") (name "Net-(D270-Cathode)") (class "Default")
      (node (ref "D270") (pin "1") (pinfunction "Cathode_1") (pintype "passive"))
      (node (ref "R270") (pin "2") (pinfunction "2_2") (pintype "passive"))
    )
    (net (code "90") (name "XMC_3V3") (class "Default")
      (node (ref "C310") (pin "1") (pinfunction "1_1") (pintype "passive"))
      (node (ref "C311") (pin "1") (pinfunction "1_1") (pintype "passive"))
      (node (ref "C312") (pin "1") (pinfunction "1_1") (pintype "passive"))
      (node (ref "C313") (pin "1") (pinfunction "1_1") (pintype "passive"))
      (node (ref "C314") (pin "1") (pinfunction "1_1") (pintype "passive"))
      (node (ref "C315") (pin "1") (pinfunction "1_1") (pintype "passive"))
      (node (ref "C316") (pin "2") (pinfunction "2_2") (pintype "passive"))
      (node (ref "C317") (pin "1") (pinfunction "1_1") (pintype "passive"))
      (node (ref "C318") (pin "1") (pinfunction "1_1") (pintype "passive"))
      (node (ref "C319") (pin "1") (pinfunction "1_1") (pintype "passive"))
      (node (ref "C320") (pin "1") (pinfunction "1_1") (pintype "passive"))
      (node (ref "C321") (pin "2") (pinfunction "2_2") (pintype "passive"))
      (node (ref "D270") (pin "2") (pinfunction "Anode_2") (pintype "passive"))
      (node (ref "JTAG_XMC_CON") (pin "1") (pinfunction "1_1") (pintype "passive"))
      (node (ref "XMC") (pin "11") (pinfunction "VDDP_1_11") (pintype "passive"))
      (node (ref "XMC") (pin "12") (pinfunction "VDDC_1_12") (pintype "passive"))
      (node (ref "XMC") (pin "33") (pinfunction "VAREF_33") (pintype "passive"))
      (node (ref "XMC") (pin "35") (pinfunction "VDDA_35") (pintype "passive"))
      (node (ref "XMC") (pin "42") (pinfunction "VDDC_2_42") (pintype "passive"))
      (node (ref "XMC") (pin "43") (pinfunction "VDDP_2_43") (pintype "passive"))
      (node (ref "XMC") (pin "60") (pinfunction "VDDP_3_60") (pintype "passive"))
      (node (ref "XMC") (pin "64") (pinfunction "VDDC_3_64") (pintype "passive"))
      (node (ref "XMC") (pin "86") (pinfunction "VDDC_4_86") (pintype "passive"))
      (node (ref "XMC") (pin "87") (pinfunction "VDDP_4_87") (pintype "passive"))
      (node (ref "XMC_SW") (pin "3") (pinfunction "3_3") (pintype "passive"))
    )
    (net (code "91") (name "unconnected-(JTAG_XMC_CON-Pad7)") (class "Default")
      (node (ref "JTAG_XMC_CON") (pin "7") (pinfunction "7_7") (pintype "passive+no_connect"))
    )
    (net (code "92") (name "unconnected-(JTAG_XMC_CON-Pad9)") (class "Default")
      (node (ref "JTAG_XMC_CON") (pin "9") (pinfunction "9_9") (pintype "passive+no_connect"))
    )
    (net (code "93") (name "unconnected-(XMC-HIB_IO__0-Pad14)") (class "Default")
      (node (ref "XMC") (pin "14") (pinfunction "HIB_IO__0_14") (pintype "passive"))
    )
    (net (code "94") (name "unconnected-(XMC-HIB_IO__1-Pad13)") (class "Default")
      (node (ref "XMC") (pin "13") (pinfunction "HIB_IO__1_13") (pintype "passive"))
    )
    (net (code "95") (name "unconnected-(XMC-USB_DM-Pad8)") (class "Default")
      (node (ref "XMC") (pin "8") (pinfunction "USB_DM_8") (pintype "passive"))
    )
    (net (code "96") (name "unconnected-(XMC-USB_DP-Pad9)") (class "Default")
      (node (ref "XMC") (pin "9") (pinfunction "USB_DP_9") (pintype "passive"))
    )
    (net (code "97") (name "unconnected-(XMC-VBAT-Pad17)") (class "Default")
      (node (ref "XMC") (pin "17") (pinfunction "VBAT_17") (pintype "passive"))
    )
    (net (code "98") (name "unconnected-(XMC-VBUS-Pad10)") (class "Default")
      (node (ref "XMC") (pin "10") (pinfunction "VBUS_10") (pintype "passive"))
    )
    (net (code "99") (name "unconnected-(XMC_SW-Pad1)") (class "Default")
      (node (ref "XMC_SW") (pin "1") (pinfunction "1_1") (pintype "passive"))
    )
  )
)
